# example.net
KiCad netlist of a schematic drawn in EAGLE
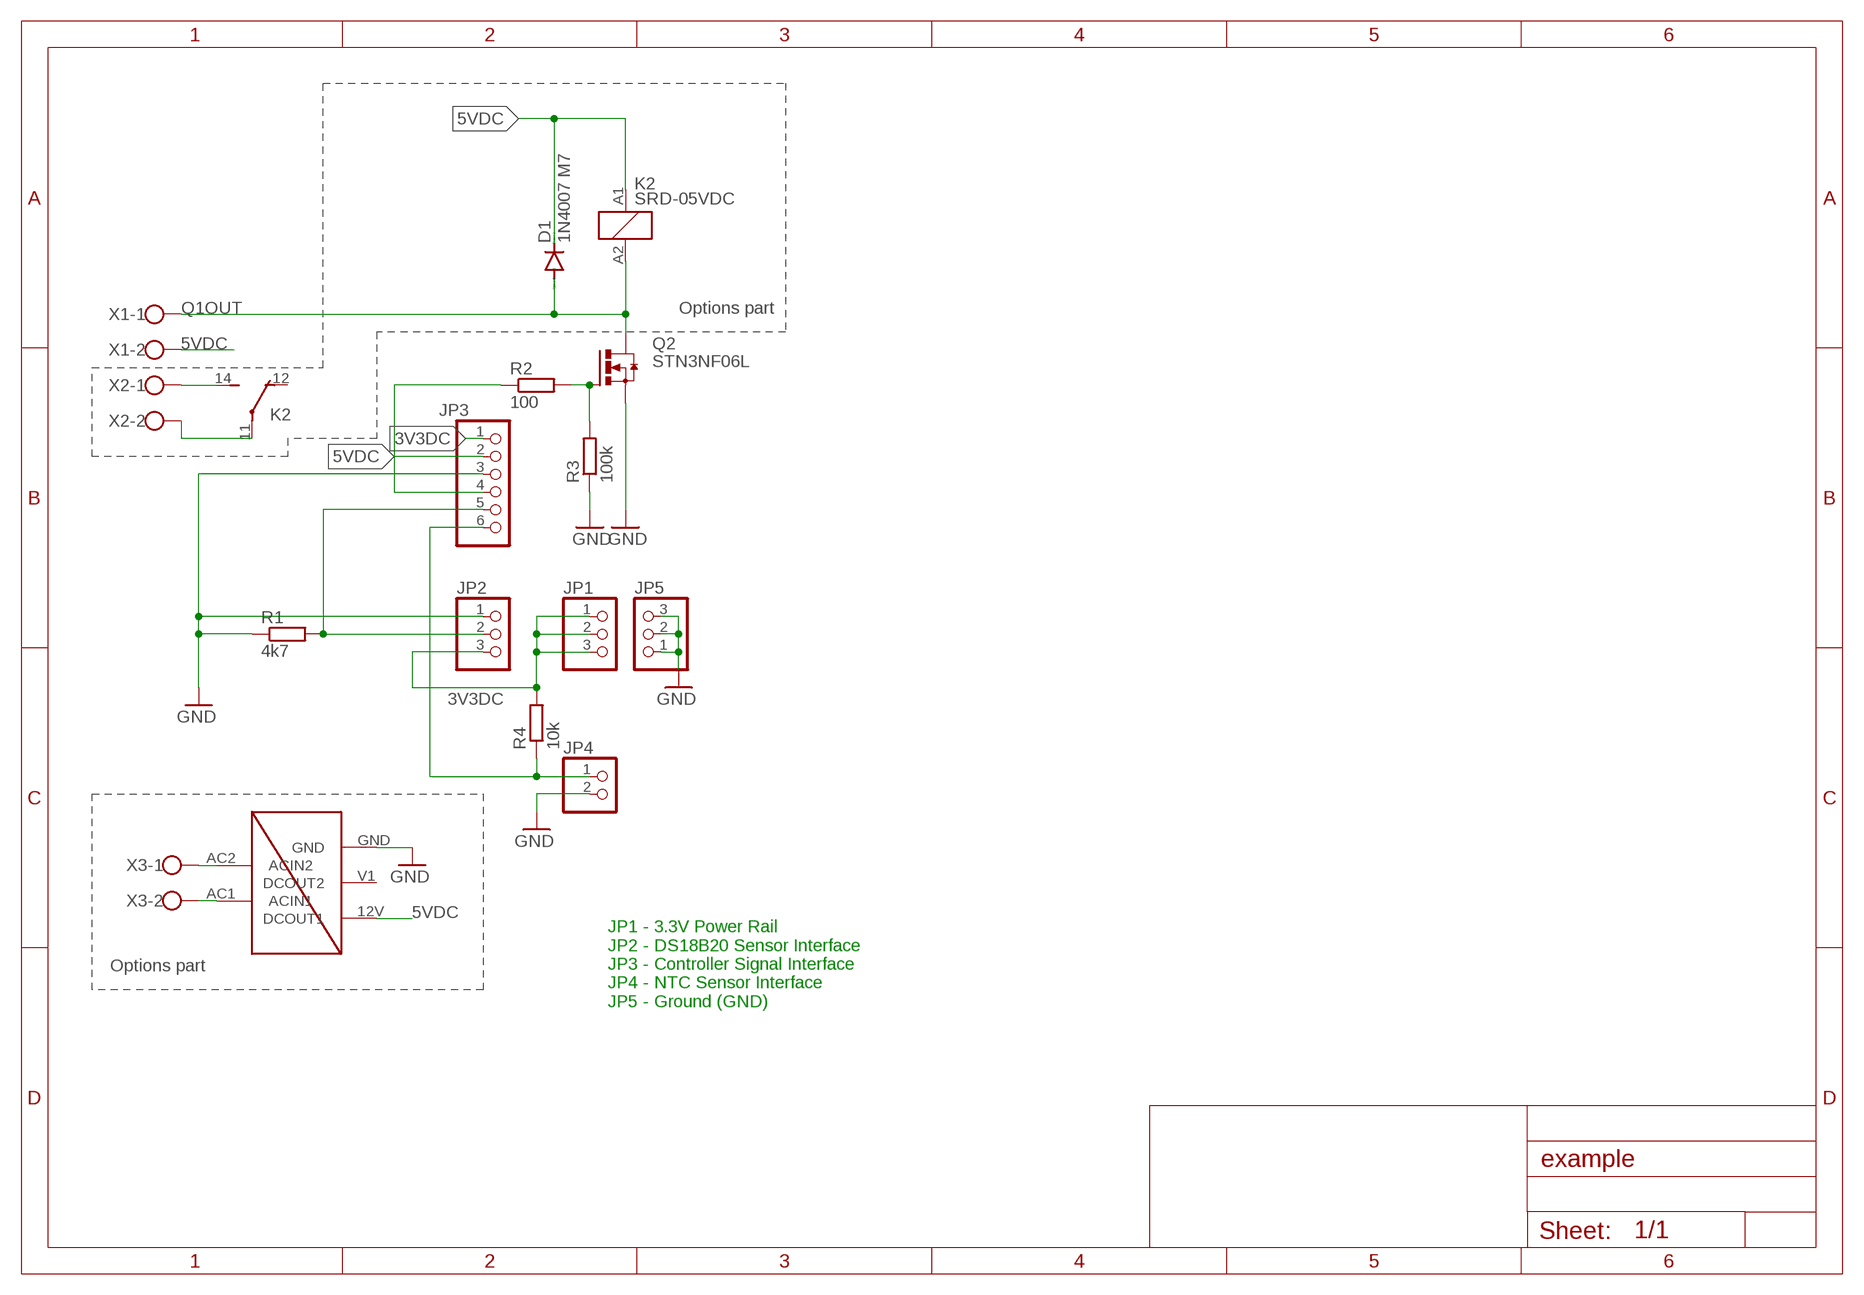
[diagram p0: schematic, sheet 1]

(export (version "E")
  (design (tool "Eeschema 10.0.6"))
  (components
    (comp (ref "D1")
      (value "1N4007 M7")
      (footprint "eagle-import:DO-214AC")
      (libsource (lib "eagle-import") (part "DIODE-DO-214AC"))
    )
    (comp (ref "JP1")
      (value "PINHD-1X3")
      (footprint "eagle-import:1X03")
      (libsource (lib "eagle-import") (part "PINHD-1X3"))
    )
    (comp (ref "JP2")
      (value "PINHD-1X3")
      (footprint "eagle-import:1X03")
      (libsource (lib "eagle-import") (part "PINHD-1X3"))
    )
    (comp (ref "JP3")
      (value "PINHD-1X6")
      (footprint "eagle-import:1X06")
      (libsource (lib "eagle-import") (part "PINHD-1X6"))
    )
    (comp (ref "JP4")
      (value "PINHD-1X2")
      (footprint "eagle-import:1X02")
      (libsource (lib "eagle-import") (part "PINHD-1X2"))
    )
    (comp (ref "JP5")
      (value "PINHD-1X3")
      (footprint "eagle-import:1X03")
      (libsource (lib "eagle-import") (part "PINHD-1X3"))
    )
    (comp (ref "K2")
      (value "SRD-05VDC")
      (footprint "eagle-import:ZN5")
      (libsource (lib "eagle-import") (part "ZNS5106"))
    )
    (comp (ref "PW")
      (value "SUPPLY12-V05")
      (footprint "eagle-import:SUPPLY-12V04")
      (libsource (lib "eagle-import") (part "SUPPLY12-V05"))
    )
    (comp (ref "Q2")
      (value "STN3NF06L")
      (footprint "eagle-import:SOT223")
      (libsource (lib "eagle-import") (part "N-HEXFET-2D_?-SOT232"))
    )
    (comp (ref "R1")
      (value "4k7")
      (footprint "eagle-import:M1206")
      (libsource (lib "eagle-import") (part "R-EU_M1206"))
    )
    (comp (ref "R2")
      (value "100")
      (footprint "eagle-import:R1206")
      (libsource (lib "eagle-import") (part "R-EU_R1206"))
    )
    (comp (ref "R3")
      (value "100k")
      (footprint "eagle-import:R1206")
      (libsource (lib "eagle-import") (part "R-EU_R1206"))
    )
    (comp (ref "R4")
      (value "10k")
      (footprint "eagle-import:R1206")
      (libsource (lib "eagle-import") (part "R-EU_R1206"))
    )
    (comp (ref "X1")
      (value "W237-102")
      (footprint "eagle-import:W237-102")
      (fields (field (name "MPN") "237-102"))
      (libsource (lib "eagle-import") (part "W237-102"))
    )
    (comp (ref "X2")
      (value "W237-102")
      (footprint "eagle-import:W237-102")
      (fields (field (name "MPN") "237-102"))
      (libsource (lib "eagle-import") (part "W237-102"))
    )
    (comp (ref "X3")
      (value "W237-102")
      (footprint "eagle-import:W237-102")
      (fields (field (name "MPN") "237-102"))
      (libsource (lib "eagle-import") (part "W237-102"))
    )
  )
  (nets
    (net (code "1") (name "/Q1OUT") (class "Default")
      (node (ref "D1") (pin "A") (pinfunction "A_A") (pintype "passive"))
      (node (ref "K2") (pin "A2") (pinfunction "2_A2") (pintype "passive"))
      (node (ref "Q2") (pin "2") (pinfunction "D_2") (pintype "passive"))
      (node (ref "Q2") (pin "4") (pinfunction "D_4") (pintype "passive"))
      (node (ref "X1") (pin "1") (pinfunction "KL_1") (pintype "passive"))
    )
    (net (code "2") (name "3V3DC") (class "Default")
      (node (ref "JP1") (pin "1") (pinfunction "1_1") (pintype "passive"))
      (node (ref "JP1") (pin "2") (pinfunction "2_2") (pintype "passive"))
      (node (ref "JP1") (pin "3") (pinfunction "3_3") (pintype "passive"))
      (node (ref "JP2") (pin "3") (pinfunction "3_3") (pintype "passive"))
      (node (ref "JP3") (pin "1") (pinfunction "1_1") (pintype "passive"))
      (node (ref "R4") (pin "2") (pinfunction "2_2") (pintype "passive"))
    )
    (net (code "3") (name "5VDC") (class "Default")
      (node (ref "D1") (pin "C") (pinfunction "C_C") (pintype "passive"))
      (node (ref "JP3") (pin "2") (pinfunction "2_2") (pintype "passive"))
      (node (ref "K2") (pin "A1") (pinfunction "1_A1") (pintype "passive"))
      (node (ref "PW") (pin "12V") (pinfunction "DCOUT1_12V") (pintype "bidirectional"))
      (node (ref "X1") (pin "2") (pinfunction "KL_2") (pintype "passive"))
    )
    (net (code "4") (name "GND") (class "Default")
      (node (ref "JP2") (pin "1") (pinfunction "1_1") (pintype "passive"))
      (node (ref "JP3") (pin "3") (pinfunction "3_3") (pintype "passive"))
      (node (ref "JP4") (pin "2") (pinfunction "2_2") (pintype "passive"))
      (node (ref "JP5") (pin "1") (pinfunction "1_1") (pintype "passive"))
      (node (ref "JP5") (pin "2") (pinfunction "2_2") (pintype "passive"))
      (node (ref "JP5") (pin "3") (pinfunction "3_3") (pintype "passive"))
      (node (ref "PW") (pin "GND") (pinfunction "GND_GND") (pintype "bidirectional"))
      (node (ref "Q2") (pin "3") (pinfunction "S_3") (pintype "passive"))
      (node (ref "R1") (pin "1") (pinfunction "1_1") (pintype "passive"))
      (node (ref "R3") (pin "1") (pinfunction "1_1") (pintype "passive"))
    )
    (net (code "5") (name "Net-(JP2-Pad2)") (class "Default")
      (node (ref "JP2") (pin "2") (pinfunction "2_2") (pintype "passive"))
      (node (ref "JP3") (pin "5") (pinfunction "5_5") (pintype "passive"))
      (node (ref "R1") (pin "2") (pinfunction "2_2") (pintype "passive"))
    )
    (net (code "6") (name "Net-(JP3-Pad4)") (class "Default")
      (node (ref "JP3") (pin "4") (pinfunction "4_4") (pintype "passive"))
      (node (ref "R2") (pin "1") (pinfunction "1_1") (pintype "passive"))
    )
    (net (code "7") (name "Net-(JP3-Pad6)") (class "Default")
      (node (ref "JP3") (pin "6") (pinfunction "6_6") (pintype "passive"))
      (node (ref "JP4") (pin "1") (pinfunction "1_1") (pintype "passive"))
      (node (ref "R4") (pin "1") (pinfunction "1_1") (pintype "passive"))
    )
    (net (code "8") (name "Net-(K2B-P)") (class "Default")
      (node (ref "K2") (pin "11") (pinfunction "P_11") (pintype "passive"))
      (node (ref "X2") (pin "2") (pinfunction "KL_2") (pintype "passive"))
    )
    (net (code "9") (name "Net-(K2B-S)") (class "Default")
      (node (ref "K2") (pin "14") (pinfunction "S_14") (pintype "passive"))
      (node (ref "X2") (pin "1") (pinfunction "KL_1") (pintype "passive"))
    )
    (net (code "10") (name "Net-(PW-ACIN1)") (class "Default")
      (node (ref "PW") (pin "AC1") (pinfunction "ACIN1_AC1") (pintype "bidirectional"))
      (node (ref "X3") (pin "2") (pinfunction "KL_2") (pintype "passive"))
    )
    (net (code "11") (name "Net-(PW-ACIN2)") (class "Default")
      (node (ref "PW") (pin "AC2") (pinfunction "ACIN2_AC2") (pintype "bidirectional"))
      (node (ref "X3") (pin "1") (pinfunction "KL_1") (pintype "passive"))
    )
    (net (code "12") (name "Net-(Q2-G)") (class "Default")
      (node (ref "Q2") (pin "1") (pinfunction "G_1") (pintype "passive"))
      (node (ref "R2") (pin "2") (pinfunction "2_2") (pintype "passive"))
      (node (ref "R3") (pin "2") (pinfunction "2_2") (pintype "passive"))
    )
    (net (code "13") (name "unconnected-(K2B-O-Pad12)") (class "Default")
      (node (ref "K2") (pin "12") (pinfunction "O_12") (pintype "passive"))
    )
    (net (code "14") (name "unconnected-(PW-DCOUT2-PadV1)") (class "Default")
      (node (ref "PW") (pin "V1") (pinfunction "DCOUT2_V1") (pintype "bidirectional"))
    )
  )
)
